# PartC.net
KiCad netlist of a schematic drawn in Altium Designer
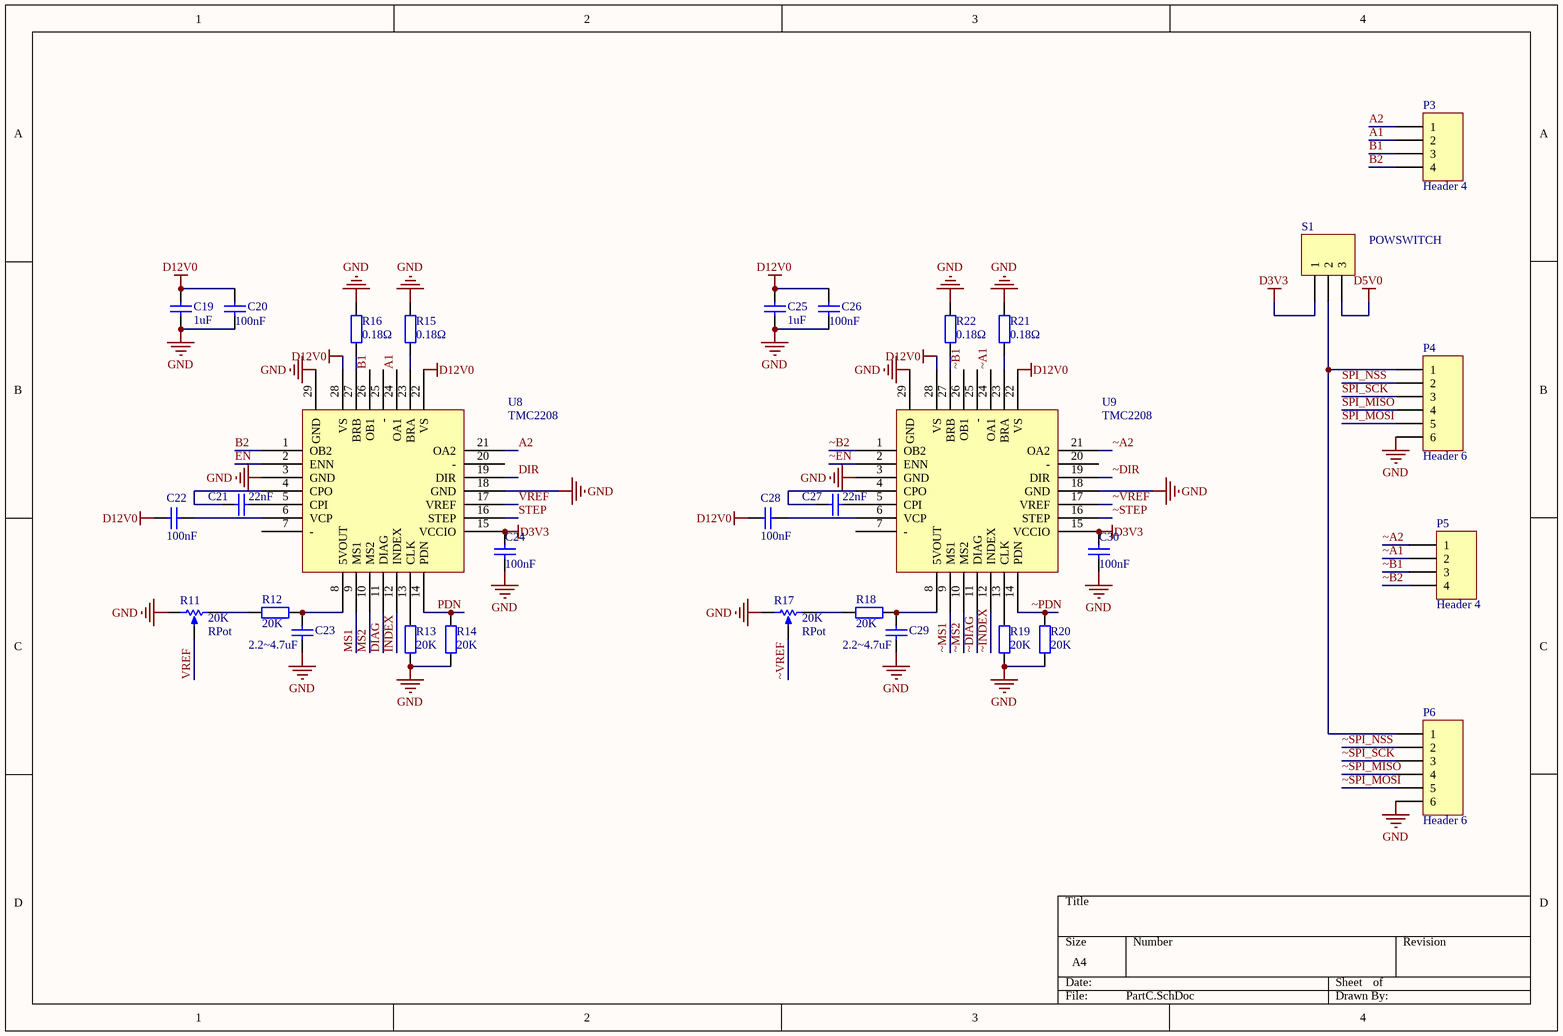
[diagram p0: PartC.SchDoc]

(export (version "E")
  (design (tool "Eeschema 10.0.6"))
  (components
    (comp (ref "C19")
      (value "1uF")
      (footprint "1206C")
      (description "Capacitor")
      (fields (field (name "PUBLISHER") "Altium Limited"))
      (libsource (lib "Crazy_PCB") (part "Cap"))
    )
    (comp (ref "C20")
      (value "100nF")
      (footprint "0603C")
      (description "Capacitor")
      (fields (field (name "PUBLISHER") "Altium Limited"))
      (libsource (lib "Crazy_PCB") (part "Cap"))
    )
    (comp (ref "C21")
      (value "22nF")
      (footprint "0603C")
      (description "Capacitor")
      (fields (field (name "PUBLISHER") "Altium Limited"))
      (libsource (lib "Crazy_PCB") (part "Cap"))
    )
    (comp (ref "C22")
      (value "100nF")
      (footprint "0603C")
      (description "Capacitor")
      (fields (field (name "PUBLISHER") "Altium Limited"))
      (libsource (lib "Crazy_PCB") (part "Cap"))
    )
    (comp (ref "C23")
      (value "2.2~4.7uF")
      (footprint "0603C")
      (description "Capacitor")
      (fields (field (name "PUBLISHER") "Altium Limited"))
      (libsource (lib "Crazy_PCB") (part "Cap"))
    )
    (comp (ref "C24")
      (value "100nF")
      (footprint "0603C")
      (description "Capacitor")
      (fields (field (name "PUBLISHER") "Altium Limited"))
      (libsource (lib "Crazy_PCB") (part "Cap"))
    )
    (comp (ref "C25")
      (value "1uF")
      (footprint "1206C")
      (description "Capacitor")
      (fields (field (name "PUBLISHER") "Altium Limited"))
      (libsource (lib "Crazy_PCB") (part "Cap"))
    )
    (comp (ref "C26")
      (value "100nF")
      (footprint "0603C")
      (description "Capacitor")
      (fields (field (name "PUBLISHER") "Altium Limited"))
      (libsource (lib "Crazy_PCB") (part "Cap"))
    )
    (comp (ref "C27")
      (value "22nF")
      (footprint "0603C")
      (description "Capacitor")
      (fields (field (name "PUBLISHER") "Altium Limited"))
      (libsource (lib "Crazy_PCB") (part "Cap"))
    )
    (comp (ref "C28")
      (value "100nF")
      (footprint "0603C")
      (description "Capacitor")
      (fields (field (name "PUBLISHER") "Altium Limited"))
      (libsource (lib "Crazy_PCB") (part "Cap"))
    )
    (comp (ref "C29")
      (value "2.2~4.7uF")
      (footprint "0603C")
      (description "Capacitor")
      (fields (field (name "PUBLISHER") "Altium Limited"))
      (libsource (lib "Crazy_PCB") (part "Cap"))
    )
    (comp (ref "C30")
      (value "100nF")
      (footprint "0603C")
      (description "Capacitor")
      (fields (field (name "PUBLISHER") "Altium Limited"))
      (libsource (lib "Crazy_PCB") (part "Cap"))
    )
    (comp (ref "P3")
      (value "Header 4")
      (footprint "XH_4_V")
      (description "Header, 4-Pin")
      (fields (field (name "PUBLISHER") "Altium Limited"))
      (libsource (lib "Miscellaneous Connectors") (part "Header 4"))
    )
    (comp (ref "P4")
      (value "Header 6")
      (footprint "XH_6_V")
      (description "Header, 6-Pin")
      (fields (field (name "PUBLISHER") "Altium Limited"))
      (libsource (lib "Miscellaneous Connectors") (part "Header 6"))
    )
    (comp (ref "P5")
      (value "Header 4")
      (footprint "XH_4_V")
      (description "Header, 4-Pin")
      (fields (field (name "PUBLISHER") "Altium Limited"))
      (libsource (lib "Miscellaneous Connectors") (part "Header 4"))
    )
    (comp (ref "P6")
      (value "Header 6")
      (footprint "XH_6_V")
      (description "Header, 6-Pin")
      (fields (field (name "PUBLISHER") "Altium Limited"))
      (libsource (lib "Miscellaneous Connectors") (part "Header 6"))
    )
    (comp (ref "R11")
      (value "RPot")
      (footprint "VR_SMD")
      (description "Potentiometer")
      (fields (field (name "ALTIUM_VALUE") "20K") (field (name "PUBLISHER") "Altium Limited"))
      (libsource (lib "Miscellaneous Devices") (part "RPot"))
    )
    (comp (ref "R12")
      (value "20K")
      (footprint "0603R")
      (description "Resistor")
      (fields (field (name "PUBLISHER") "Altium Limited"))
      (libsource (lib "Crazy_PCB") (part "RES"))
    )
    (comp (ref "R13")
      (value "20K")
      (footprint "0603R")
      (description "Resistor")
      (fields (field (name "PUBLISHER") "Altium Limited"))
      (libsource (lib "") (part "RES_2"))
    )
    (comp (ref "R14")
      (value "20K")
      (footprint "0603R")
      (description "Resistor")
      (fields (field (name "PUBLISHER") "Altium Limited"))
      (libsource (lib "") (part "RES_2"))
    )
    (comp (ref "R15")
      (value "0.18Ω")
      (footprint "1206R")
      (description "Resistor")
      (fields (field (name "PUBLISHER") "Altium Limited"))
      (libsource (lib "") (part "RES_1"))
    )
    (comp (ref "R16")
      (value "0.18Ω")
      (footprint "1206R")
      (description "Resistor")
      (fields (field (name "PUBLISHER") "Altium Limited"))
      (libsource (lib "") (part "RES_1"))
    )
    (comp (ref "R17")
      (value "RPot")
      (footprint "VR_SMD")
      (description "Potentiometer")
      (fields (field (name "ALTIUM_VALUE") "20K") (field (name "PUBLISHER") "Altium Limited"))
      (libsource (lib "Miscellaneous Devices") (part "RPot"))
    )
    (comp (ref "R18")
      (value "20K")
      (footprint "0603R")
      (description "Resistor")
      (fields (field (name "PUBLISHER") "Altium Limited"))
      (libsource (lib "Crazy_PCB") (part "RES"))
    )
    (comp (ref "R19")
      (value "20K")
      (footprint "0603R")
      (description "Resistor")
      (fields (field (name "PUBLISHER") "Altium Limited"))
      (libsource (lib "") (part "RES_2"))
    )
    (comp (ref "R20")
      (value "20K")
      (footprint "0603R")
      (description "Resistor")
      (fields (field (name "PUBLISHER") "Altium Limited"))
      (libsource (lib "") (part "RES_2"))
    )
    (comp (ref "R21")
      (value "0.18Ω")
      (footprint "1206R")
      (description "Resistor")
      (fields (field (name "PUBLISHER") "Altium Limited"))
      (libsource (lib "") (part "RES_1"))
    )
    (comp (ref "R22")
      (value "0.18Ω")
      (footprint "1206R")
      (description "Resistor")
      (fields (field (name "PUBLISHER") "Altium Limited"))
      (libsource (lib "") (part "RES_1"))
    )
    (comp (ref "S1")
      (value "POWSWITCH")
      (footprint "HDR1X3")
      (description "Header, 3-Pin, Right Angle")
      (fields (field (name "PUBLISHER") "Altium Limited"))
      (libsource (lib "JL_SCH") (part "Header 3H"))
    )
    (comp (ref "U8") (value "TMC2208") (footprint "QFN28 5x5_M") (libsource (lib "SS") (part "TMC2208")))
    (comp (ref "U9") (value "TMC2208") (footprint "QFN28 5x5_M") (libsource (lib "SS") (part "TMC2208")))
  )
  (nets
    (net (code "1") (name "/A1") (class "Default")
      (node (ref "P3") (pin "2") (pinfunction "2_2") (pintype "passive"))
      (node (ref "U8") (pin "24") (pinfunction "OA1_24") (pintype "passive"))
    )
    (net (code "2") (name "/A2") (class "Default")
      (node (ref "P3") (pin "1") (pinfunction "1_1") (pintype "passive"))
      (node (ref "U8") (pin "21") (pinfunction "OA2_21") (pintype "passive"))
    )
    (net (code "3") (name "/B1") (class "Default")
      (node (ref "P3") (pin "3") (pinfunction "3_3") (pintype "passive"))
      (node (ref "U8") (pin "26") (pinfunction "OB1_26") (pintype "passive"))
    )
    (net (code "4") (name "/B2") (class "Default")
      (node (ref "P3") (pin "4") (pinfunction "4_4") (pintype "passive"))
      (node (ref "U8") (pin "1") (pinfunction "OB2_1") (pintype "passive"))
    )
    (net (code "5") (name "/DIAG") (class "Default")
      (node (ref "U8") (pin "11") (pinfunction "DIAG_11") (pintype "passive"))
    )
    (net (code "6") (name "/DIR") (class "Default")
      (node (ref "U8") (pin "19") (pinfunction "DIR_19") (pintype "passive"))
    )
    (net (code "7") (name "/EN") (class "Default")
      (node (ref "U8") (pin "2") (pinfunction "ENN_2") (pintype "passive"))
    )
    (net (code "8") (name "/INDEX") (class "Default")
      (node (ref "U8") (pin "12") (pinfunction "INDEX_12") (pintype "passive"))
    )
    (net (code "9") (name "/MS1") (class "Default")
      (node (ref "U8") (pin "9") (pinfunction "MS1_9") (pintype "passive"))
    )
    (net (code "10") (name "/MS2") (class "Default")
      (node (ref "U8") (pin "10") (pinfunction "MS2_10") (pintype "passive"))
    )
    (net (code "11") (name "/PDN") (class "Default")
      (node (ref "R14") (pin "2") (pinfunction "2_2") (pintype "passive"))
      (node (ref "U8") (pin "14") (pinfunction "PDN_14") (pintype "passive"))
    )
    (net (code "12") (name "/SPI_MISO") (class "Default")
      (node (ref "P4") (pin "4") (pinfunction "4_4") (pintype "passive"))
    )
    (net (code "13") (name "/SPI_MOSI") (class "Default")
      (node (ref "P4") (pin "5") (pinfunction "5_5") (pintype "passive"))
    )
    (net (code "14") (name "/SPI_NSS") (class "Default")
      (node (ref "P4") (pin "2") (pinfunction "2_2") (pintype "passive"))
    )
    (net (code "15") (name "/SPI_SCK") (class "Default")
      (node (ref "P4") (pin "3") (pinfunction "3_3") (pintype "passive"))
    )
    (net (code "16") (name "/STEP") (class "Default")
      (node (ref "U8") (pin "16") (pinfunction "STEP_16") (pintype "passive"))
    )
    (net (code "17") (name "/VREF") (class "Default")
      (node (ref "R11") (pin "3") (pinfunction "TAP_3") (pintype "passive"))
      (node (ref "U8") (pin "17") (pinfunction "VREF_17") (pintype "passive"))
    )
    (net (code "18") (name "/~A1") (class "Default")
      (node (ref "P5") (pin "2") (pinfunction "2_2") (pintype "passive"))
      (node (ref "U9") (pin "24") (pinfunction "OA1_24") (pintype "passive"))
    )
    (net (code "19") (name "/~A2") (class "Default")
      (node (ref "P5") (pin "1") (pinfunction "1_1") (pintype "passive"))
      (node (ref "U9") (pin "21") (pinfunction "OA2_21") (pintype "passive"))
    )
    (net (code "20") (name "/~B1") (class "Default")
      (node (ref "P5") (pin "3") (pinfunction "3_3") (pintype "passive"))
      (node (ref "U9") (pin "26") (pinfunction "OB1_26") (pintype "passive"))
    )
    (net (code "21") (name "/~B2") (class "Default")
      (node (ref "P5") (pin "4") (pinfunction "4_4") (pintype "passive"))
      (node (ref "U9") (pin "1") (pinfunction "OB2_1") (pintype "passive"))
    )
    (net (code "22") (name "/~DIAG") (class "Default")
      (node (ref "U9") (pin "11") (pinfunction "DIAG_11") (pintype "passive"))
    )
    (net (code "23") (name "/~DIR") (class "Default")
      (node (ref "U9") (pin "19") (pinfunction "DIR_19") (pintype "passive"))
    )
    (net (code "24") (name "/~EN") (class "Default")
      (node (ref "U9") (pin "2") (pinfunction "ENN_2") (pintype "passive"))
    )
    (net (code "25") (name "/~INDEX") (class "Default")
      (node (ref "U9") (pin "12") (pinfunction "INDEX_12") (pintype "passive"))
    )
    (net (code "26") (name "/~MS1") (class "Default")
      (node (ref "U9") (pin "9") (pinfunction "MS1_9") (pintype "passive"))
    )
    (net (code "27") (name "/~MS2") (class "Default")
      (node (ref "U9") (pin "10") (pinfunction "MS2_10") (pintype "passive"))
    )
    (net (code "28") (name "/~PDN") (class "Default")
      (node (ref "R20") (pin "2") (pinfunction "2_2") (pintype "passive"))
      (node (ref "U9") (pin "14") (pinfunction "PDN_14") (pintype "passive"))
    )
    (net (code "29") (name "/~SPI_MISO") (class "Default")
      (node (ref "P6") (pin "4") (pinfunction "4_4") (pintype "passive"))
    )
    (net (code "30") (name "/~SPI_MOSI") (class "Default")
      (node (ref "P6") (pin "5") (pinfunction "5_5") (pintype "passive"))
    )
    (net (code "31") (name "/~SPI_NSS") (class "Default")
      (node (ref "P6") (pin "2") (pinfunction "2_2") (pintype "passive"))
    )
    (net (code "32") (name "/~SPI_SCK") (class "Default")
      (node (ref "P6") (pin "3") (pinfunction "3_3") (pintype "passive"))
    )
    (net (code "33") (name "/~STEP") (class "Default")
      (node (ref "U9") (pin "16") (pinfunction "STEP_16") (pintype "passive"))
    )
    (net (code "34") (name "/~VREF") (class "Default")
      (node (ref "R17") (pin "3") (pinfunction "TAP_3") (pintype "passive"))
      (node (ref "U9") (pin "17") (pinfunction "VREF_17") (pintype "passive"))
    )
    (net (code "35") (name "D3V3") (class "Default")
      (node (ref "C24") (pin "2") (pinfunction "2_2") (pintype "passive"))
      (node (ref "C30") (pin "2") (pinfunction "2_2") (pintype "passive"))
      (node (ref "S1") (pin "1") (pinfunction "1_1") (pintype "passive"))
      (node (ref "U8") (pin "15") (pinfunction "VCCIO_15") (pintype "passive"))
      (node (ref "U9") (pin "15") (pinfunction "VCCIO_15") (pintype "passive"))
    )
    (net (code "36") (name "D5V0") (class "Default")
      (node (ref "S1") (pin "3") (pinfunction "3_3") (pintype "passive"))
    )
    (net (code "37") (name "D12V0") (class "Default")
      (node (ref "C19") (pin "1") (pinfunction "1_1") (pintype "passive"))
      (node (ref "C20") (pin "2") (pinfunction "2_2") (pintype "passive"))
      (node (ref "C22") (pin "2") (pinfunction "2_2") (pintype "passive"))
      (node (ref "C25") (pin "1") (pinfunction "1_1") (pintype "passive"))
      (node (ref "C26") (pin "2") (pinfunction "2_2") (pintype "passive"))
      (node (ref "C28") (pin "2") (pinfunction "2_2") (pintype "passive"))
      (node (ref "U8") (pin "22") (pinfunction "VS_22") (pintype "passive"))
      (node (ref "U8") (pin "28") (pinfunction "VS_28") (pintype "passive"))
      (node (ref "U9") (pin "22") (pinfunction "VS_22") (pintype "passive"))
      (node (ref "U9") (pin "28") (pinfunction "VS_28") (pintype "passive"))
    )
    (net (code "38") (name "GND") (class "Default")
      (node (ref "C19") (pin "2") (pinfunction "2_2") (pintype "passive"))
      (node (ref "C20") (pin "1") (pinfunction "1_1") (pintype "passive"))
      (node (ref "C23") (pin "1") (pinfunction "1_1") (pintype "passive"))
      (node (ref "C24") (pin "1") (pinfunction "1_1") (pintype "passive"))
      (node (ref "C25") (pin "2") (pinfunction "2_2") (pintype "passive"))
      (node (ref "C26") (pin "1") (pinfunction "1_1") (pintype "passive"))
      (node (ref "C29") (pin "1") (pinfunction "1_1") (pintype "passive"))
      (node (ref "C30") (pin "1") (pinfunction "1_1") (pintype "passive"))
      (node (ref "P4") (pin "6") (pinfunction "6_6") (pintype "passive"))
      (node (ref "P6") (pin "6") (pinfunction "6_6") (pintype "passive"))
      (node (ref "R11") (pin "1") (pinfunction "TOP_1") (pintype "passive"))
      (node (ref "R13") (pin "1") (pinfunction "1_1") (pintype "passive"))
      (node (ref "R14") (pin "1") (pinfunction "1_1") (pintype "passive"))
      (node (ref "R15") (pin "1") (pinfunction "1_1") (pintype "passive"))
      (node (ref "R16") (pin "1") (pinfunction "1_1") (pintype "passive"))
      (node (ref "R17") (pin "1") (pinfunction "TOP_1") (pintype "passive"))
      (node (ref "R19") (pin "1") (pinfunction "1_1") (pintype "passive"))
      (node (ref "R20") (pin "1") (pinfunction "1_1") (pintype "passive"))
      (node (ref "R21") (pin "1") (pinfunction "1_1") (pintype "passive"))
      (node (ref "R22") (pin "1") (pinfunction "1_1") (pintype "passive"))
      (node (ref "U8") (pin "18") (pinfunction "GND_18") (pintype "passive"))
      (node (ref "U8") (pin "29") (pinfunction "GND_29") (pintype "passive"))
      (node (ref "U8") (pin "3") (pinfunction "GND_3") (pintype "passive"))
      (node (ref "U9") (pin "18") (pinfunction "GND_18") (pintype "passive"))
      (node (ref "U9") (pin "29") (pinfunction "GND_29") (pintype "passive"))
      (node (ref "U9") (pin "3") (pinfunction "GND_3") (pintype "passive"))
    )
    (net (code "39") (name "Net-(P4-Pad1)") (class "Default")
      (node (ref "P4") (pin "1") (pinfunction "1_1") (pintype "passive"))
      (node (ref "P6") (pin "1") (pinfunction "1_1") (pintype "passive"))
      (node (ref "S1") (pin "2") (pinfunction "2_2") (pintype "passive"))
    )
    (net (code "40") (name "Net-(R11-BOT)") (class "Default")
      (node (ref "R11") (pin "2") (pinfunction "BOT_2") (pintype "passive"))
      (node (ref "R12") (pin "2") (pinfunction "2_2") (pintype "passive"))
    )
    (net (code "41") (name "Net-(R17-BOT)") (class "Default")
      (node (ref "R17") (pin "2") (pinfunction "BOT_2") (pintype "passive"))
      (node (ref "R18") (pin "2") (pinfunction "2_2") (pintype "passive"))
    )
    (net (code "42") (name "Net-(U8-5VOUT)") (class "Default")
      (node (ref "C23") (pin "2") (pinfunction "2_2") (pintype "passive"))
      (node (ref "R12") (pin "1") (pinfunction "1_1") (pintype "passive"))
      (node (ref "U8") (pin "8") (pinfunction "5VOUT_8") (pintype "passive"))
    )
    (net (code "43") (name "Net-(U8-BRA)") (class "Default")
      (node (ref "R15") (pin "2") (pinfunction "2_2") (pintype "passive"))
      (node (ref "U8") (pin "23") (pinfunction "BRA_23") (pintype "passive"))
    )
    (net (code "44") (name "Net-(U8-BRB)") (class "Default")
      (node (ref "R16") (pin "2") (pinfunction "2_2") (pintype "passive"))
      (node (ref "U8") (pin "27") (pinfunction "BRB_27") (pintype "passive"))
    )
    (net (code "45") (name "Net-(U8-CLK)") (class "Default")
      (node (ref "R13") (pin "2") (pinfunction "2_2") (pintype "passive"))
      (node (ref "U8") (pin "13") (pinfunction "CLK_13") (pintype "passive"))
    )
    (net (code "46") (name "Net-(U8-CPI)") (class "Default")
      (node (ref "C21") (pin "1") (pinfunction "1_1") (pintype "passive"))
      (node (ref "U8") (pin "5") (pinfunction "CPI_5") (pintype "passive"))
    )
    (net (code "47") (name "Net-(U8-CPO)") (class "Default")
      (node (ref "C21") (pin "2") (pinfunction "2_2") (pintype "passive"))
      (node (ref "U8") (pin "4") (pinfunction "CPO_4") (pintype "passive"))
    )
    (net (code "48") (name "Net-(U8-VCP)") (class "Default")
      (node (ref "C22") (pin "1") (pinfunction "1_1") (pintype "passive"))
      (node (ref "U8") (pin "6") (pinfunction "VCP_6") (pintype "passive"))
    )
    (net (code "49") (name "Net-(U9-5VOUT)") (class "Default")
      (node (ref "C29") (pin "2") (pinfunction "2_2") (pintype "passive"))
      (node (ref "R18") (pin "1") (pinfunction "1_1") (pintype "passive"))
      (node (ref "U9") (pin "8") (pinfunction "5VOUT_8") (pintype "passive"))
    )
    (net (code "50") (name "Net-(U9-BRA)") (class "Default")
      (node (ref "R21") (pin "2") (pinfunction "2_2") (pintype "passive"))
      (node (ref "U9") (pin "23") (pinfunction "BRA_23") (pintype "passive"))
    )
    (net (code "51") (name "Net-(U9-BRB)") (class "Default")
      (node (ref "R22") (pin "2") (pinfunction "2_2") (pintype "passive"))
      (node (ref "U9") (pin "27") (pinfunction "BRB_27") (pintype "passive"))
    )
    (net (code "52") (name "Net-(U9-CLK)") (class "Default")
      (node (ref "R19") (pin "2") (pinfunction "2_2") (pintype "passive"))
      (node (ref "U9") (pin "13") (pinfunction "CLK_13") (pintype "passive"))
    )
    (net (code "53") (name "Net-(U9-CPI)") (class "Default")
      (node (ref "C27") (pin "1") (pinfunction "1_1") (pintype "passive"))
      (node (ref "U9") (pin "5") (pinfunction "CPI_5") (pintype "passive"))
    )
    (net (code "54") (name "Net-(U9-CPO)") (class "Default")
      (node (ref "C27") (pin "2") (pinfunction "2_2") (pintype "passive"))
      (node (ref "U9") (pin "4") (pinfunction "CPO_4") (pintype "passive"))
    )
    (net (code "55") (name "Net-(U9-VCP)") (class "Default")
      (node (ref "C28") (pin "1") (pinfunction "1_1") (pintype "passive"))
      (node (ref "U9") (pin "6") (pinfunction "VCP_6") (pintype "passive"))
    )
    (net (code "56") (name "unconnected-(U8---Pad7)") (class "Default")
      (node (ref "U8") (pin "7") (pinfunction "-_7") (pintype "passive"))
    )
    (net (code "57") (name "unconnected-(U8---Pad20)") (class "Default")
      (node (ref "U8") (pin "20") (pinfunction "-_20") (pintype "passive"))
    )
    (net (code "58") (name "unconnected-(U8---Pad25)") (class "Default")
      (node (ref "U8") (pin "25") (pinfunction "-_25") (pintype "passive"))
    )
    (net (code "59") (name "unconnected-(U9---Pad7)") (class "Default")
      (node (ref "U9") (pin "7") (pinfunction "-_7") (pintype "passive"))
    )
    (net (code "60") (name "unconnected-(U9---Pad20)") (class "Default")
      (node (ref "U9") (pin "20") (pinfunction "-_20") (pintype "passive"))
    )
    (net (code "61") (name "unconnected-(U9---Pad25)") (class "Default")
      (node (ref "U9") (pin "25") (pinfunction "-_25") (pintype "passive"))
    )
  )
)
